# SCH_SIT210_PCB_Files_2022-05-17.net
KiCad netlist of a schematic drawn in EasyEDA
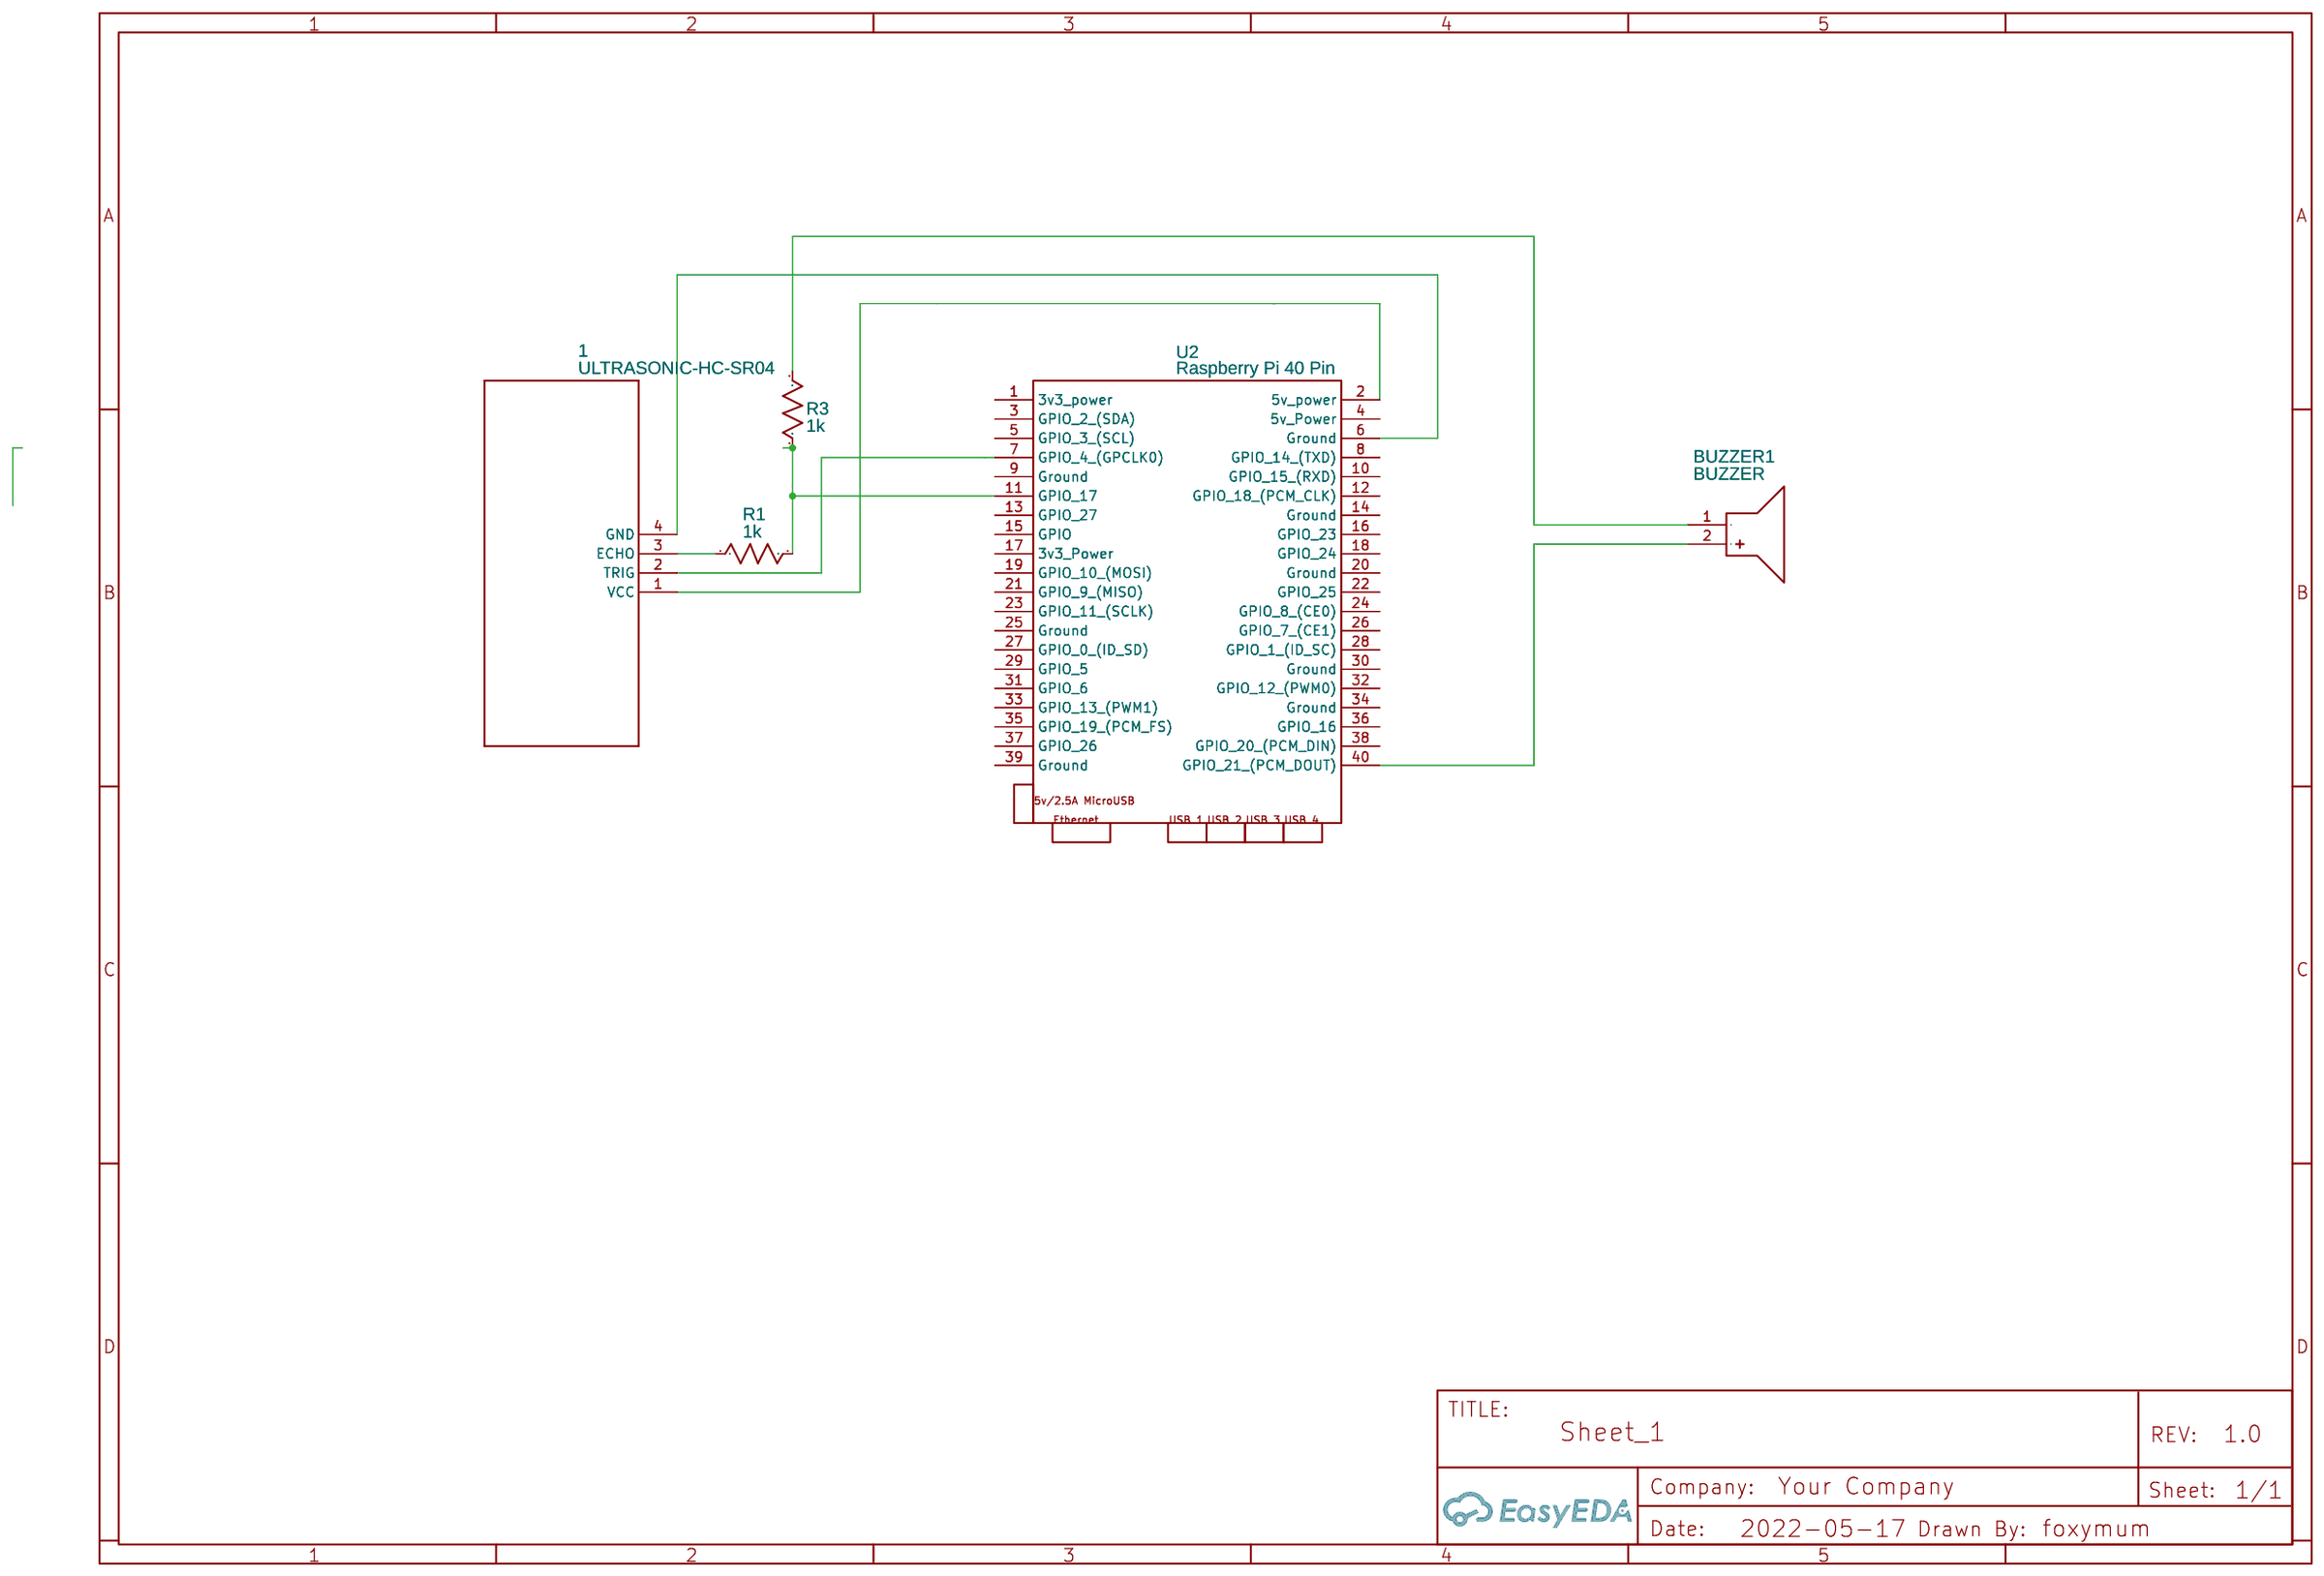
[diagram p0: schematic sheet]

(export (version "E")
  (design (tool "Eeschema 10.0.6"))
  (components
    (comp (ref "1") (value "ULTRASONIC-HC-SR04") (libsource (lib "") (part "ULTRASONIC-HC-SR04")))
    (comp (ref "BUZZER1")
      (value "BUZZER")
      (fields
        (field (name "BOM_Manufacturer Part") "buzzer")
        (field (name "BOM_Supplier Part") "C9900014030")
      )
      (libsource (lib "") (part "BUZZER"))
    )
    (comp (ref "R1") (value "1k") (libsource (lib "") (part "R_0603_US_1")))
    (comp (ref "R3") (value "1k") (libsource (lib "") (part "R_0603_US")))
    (comp (ref "U2") (value "Raspberry Pi 40 Pin") (libsource (lib "") (part "Raspberry Pi 40 Pin")))
  )
  (nets
    (net (code "1") (name "Net-(1-ECHO)") (class "Default")
      (node (ref "1") (pin "3") (pinfunction "ECHO_3") (pintype "bidirectional"))
      (node (ref "R1") (pin "1") (pinfunction "1_1") (pintype "unspecified"))
    )
    (net (code "2") (name "Net-(1-GND)") (class "Default")
      (node (ref "1") (pin "4") (pinfunction "GND_4") (pintype "bidirectional"))
      (node (ref "U2") (pin "6") (pinfunction "Ground_6") (pintype "unspecified"))
    )
    (net (code "3") (name "Net-(1-TRIG)") (class "Default")
      (node (ref "1") (pin "2") (pinfunction "TRIG_2") (pintype "bidirectional"))
      (node (ref "U2") (pin "7") (pinfunction "GPIO_4_(GPCLK0)_7") (pintype "unspecified"))
    )
    (net (code "4") (name "Net-(1-VCC)") (class "Default")
      (node (ref "1") (pin "1") (pinfunction "VCC_1") (pintype "bidirectional"))
      (node (ref "U2") (pin "2") (pinfunction "5v_power_2") (pintype "unspecified"))
    )
    (net (code "5") (name "Net-(BUZZER1-+)") (class "Default")
      (node (ref "BUZZER1") (pin "2") (pinfunction "+_2") (pintype "unspecified"))
      (node (ref "U2") (pin "40") (pinfunction "GPIO_21_(PCM_DOUT)_40") (pintype "unspecified"))
    )
    (net (code "6") (name "Net-(BUZZER1--)") (class "Default")
      (node (ref "BUZZER1") (pin "1") (pinfunction "-_1") (pintype "unspecified"))
      (node (ref "R3") (pin "2") (pinfunction "2_2") (pintype "unspecified"))
    )
    (net (code "7") (name "Net-(U2-GPIO_17)") (class "Default")
      (node (ref "R1") (pin "2") (pinfunction "2_2") (pintype "unspecified"))
      (node (ref "R3") (pin "1") (pinfunction "1_1") (pintype "unspecified"))
      (node (ref "U2") (pin "11") (pinfunction "GPIO_17_11") (pintype "unspecified"))
    )
    (net (code "8") (name "unconnected-(U2-3v3_Power-Pad17)") (class "Default")
      (node (ref "U2") (pin "17") (pinfunction "3v3_Power_17") (pintype "unspecified"))
    )
    (net (code "9") (name "unconnected-(U2-3v3_power-Pad1)") (class "Default")
      (node (ref "U2") (pin "1") (pinfunction "3v3_power_1") (pintype "unspecified"))
    )
    (net (code "10") (name "unconnected-(U2-5v_Power-Pad4)") (class "Default")
      (node (ref "U2") (pin "4") (pinfunction "5v_Power_4") (pintype "unspecified"))
    )
    (net (code "11") (name "unconnected-(U2-GPIO-Pad15)") (class "Default")
      (node (ref "U2") (pin "15") (pinfunction "GPIO_15") (pintype "unspecified"))
    )
    (net (code "12") (name "unconnected-(U2-GPIO_0_(ID_SD)-Pad27)") (class "Default")
      (node (ref "U2") (pin "27") (pinfunction "GPIO_0_(ID_SD)_27") (pintype "unspecified"))
    )
    (net (code "13") (name "unconnected-(U2-GPIO_1_(ID_SC)-Pad28)") (class "Default")
      (node (ref "U2") (pin "28") (pinfunction "GPIO_1_(ID_SC)_28") (pintype "unspecified"))
    )
    (net (code "14") (name "unconnected-(U2-GPIO_2_(SDA)-Pad3)") (class "Default")
      (node (ref "U2") (pin "3") (pinfunction "GPIO_2_(SDA)_3") (pintype "unspecified"))
    )
    (net (code "15") (name "unconnected-(U2-GPIO_3_(SCL)-Pad5)") (class "Default")
      (node (ref "U2") (pin "5") (pinfunction "GPIO_3_(SCL)_5") (pintype "unspecified"))
    )
    (net (code "16") (name "unconnected-(U2-GPIO_5-Pad29)") (class "Default")
      (node (ref "U2") (pin "29") (pinfunction "GPIO_5_29") (pintype "unspecified"))
    )
    (net (code "17") (name "unconnected-(U2-GPIO_6-Pad31)") (class "Default")
      (node (ref "U2") (pin "31") (pinfunction "GPIO_6_31") (pintype "unspecified"))
    )
    (net (code "18") (name "unconnected-(U2-GPIO_7_(CE1)-Pad26)") (class "Default")
      (node (ref "U2") (pin "26") (pinfunction "GPIO_7_(CE1)_26") (pintype "unspecified"))
    )
    (net (code "19") (name "unconnected-(U2-GPIO_8_(CE0)-Pad24)") (class "Default")
      (node (ref "U2") (pin "24") (pinfunction "GPIO_8_(CE0)_24") (pintype "unspecified"))
    )
    (net (code "20") (name "unconnected-(U2-GPIO_9_(MISO)-Pad21)") (class "Default")
      (node (ref "U2") (pin "21") (pinfunction "GPIO_9_(MISO)_21") (pintype "unspecified"))
    )
    (net (code "21") (name "unconnected-(U2-GPIO_10_(MOSI)-Pad19)") (class "Default")
      (node (ref "U2") (pin "19") (pinfunction "GPIO_10_(MOSI)_19") (pintype "unspecified"))
    )
    (net (code "22") (name "unconnected-(U2-GPIO_11_(SCLK)-Pad23)") (class "Default")
      (node (ref "U2") (pin "23") (pinfunction "GPIO_11_(SCLK)_23") (pintype "unspecified"))
    )
    (net (code "23") (name "unconnected-(U2-GPIO_12_(PWM0)-Pad32)") (class "Default")
      (node (ref "U2") (pin "32") (pinfunction "GPIO_12_(PWM0)_32") (pintype "unspecified"))
    )
    (net (code "24") (name "unconnected-(U2-GPIO_13_(PWM1)-Pad33)") (class "Default")
      (node (ref "U2") (pin "33") (pinfunction "GPIO_13_(PWM1)_33") (pintype "unspecified"))
    )
    (net (code "25") (name "unconnected-(U2-GPIO_14_(TXD)-Pad8)") (class "Default")
      (node (ref "U2") (pin "8") (pinfunction "GPIO_14_(TXD)_8") (pintype "unspecified"))
    )
    (net (code "26") (name "unconnected-(U2-GPIO_15_(RXD)-Pad10)") (class "Default")
      (node (ref "U2") (pin "10") (pinfunction "GPIO_15_(RXD)_10") (pintype "unspecified"))
    )
    (net (code "27") (name "unconnected-(U2-GPIO_16-Pad36)") (class "Default")
      (node (ref "U2") (pin "36") (pinfunction "GPIO_16_36") (pintype "unspecified"))
    )
    (net (code "28") (name "unconnected-(U2-GPIO_18_(PCM_CLK)-Pad12)") (class "Default")
      (node (ref "U2") (pin "12") (pinfunction "GPIO_18_(PCM_CLK)_12") (pintype "unspecified"))
    )
    (net (code "29") (name "unconnected-(U2-GPIO_19_(PCM_FS)-Pad35)") (class "Default")
      (node (ref "U2") (pin "35") (pinfunction "GPIO_19_(PCM_FS)_35") (pintype "unspecified"))
    )
    (net (code "30") (name "unconnected-(U2-GPIO_20_(PCM_DIN)-Pad38)") (class "Default")
      (node (ref "U2") (pin "38") (pinfunction "GPIO_20_(PCM_DIN)_38") (pintype "unspecified"))
    )
    (net (code "31") (name "unconnected-(U2-GPIO_23-Pad16)") (class "Default")
      (node (ref "U2") (pin "16") (pinfunction "GPIO_23_16") (pintype "unspecified"))
    )
    (net (code "32") (name "unconnected-(U2-GPIO_24-Pad18)") (class "Default")
      (node (ref "U2") (pin "18") (pinfunction "GPIO_24_18") (pintype "unspecified"))
    )
    (net (code "33") (name "unconnected-(U2-GPIO_25-Pad22)") (class "Default")
      (node (ref "U2") (pin "22") (pinfunction "GPIO_25_22") (pintype "unspecified"))
    )
    (net (code "34") (name "unconnected-(U2-GPIO_26-Pad37)") (class "Default")
      (node (ref "U2") (pin "37") (pinfunction "GPIO_26_37") (pintype "unspecified"))
    )
    (net (code "35") (name "unconnected-(U2-GPIO_27-Pad13)") (class "Default")
      (node (ref "U2") (pin "13") (pinfunction "GPIO_27_13") (pintype "unspecified"))
    )
    (net (code "36") (name "unconnected-(U2-Ground-Pad9)") (class "Default")
      (node (ref "U2") (pin "9") (pinfunction "Ground_9") (pintype "unspecified"))
    )
    (net (code "37") (name "unconnected-(U2-Ground-Pad14)") (class "Default")
      (node (ref "U2") (pin "14") (pinfunction "Ground_14") (pintype "unspecified"))
    )
    (net (code "38") (name "unconnected-(U2-Ground-Pad20)") (class "Default")
      (node (ref "U2") (pin "20") (pinfunction "Ground_20") (pintype "unspecified"))
    )
    (net (code "39") (name "unconnected-(U2-Ground-Pad25)") (class "Default")
      (node (ref "U2") (pin "25") (pinfunction "Ground_25") (pintype "unspecified"))
    )
    (net (code "40") (name "unconnected-(U2-Ground-Pad30)") (class "Default")
      (node (ref "U2") (pin "30") (pinfunction "Ground_30") (pintype "unspecified"))
    )
    (net (code "41") (name "unconnected-(U2-Ground-Pad34)") (class "Default")
      (node (ref "U2") (pin "34") (pinfunction "Ground_34") (pintype "unspecified"))
    )
    (net (code "42") (name "unconnected-(U2-Ground-Pad39)") (class "Default")
      (node (ref "U2") (pin "39") (pinfunction "Ground_39") (pintype "unspecified"))
    )
  )
)
